# GPS_radiologger_v24_L70_CMWX_MAX_v9.net
KiCad netlist of a schematic drawn in EAGLE
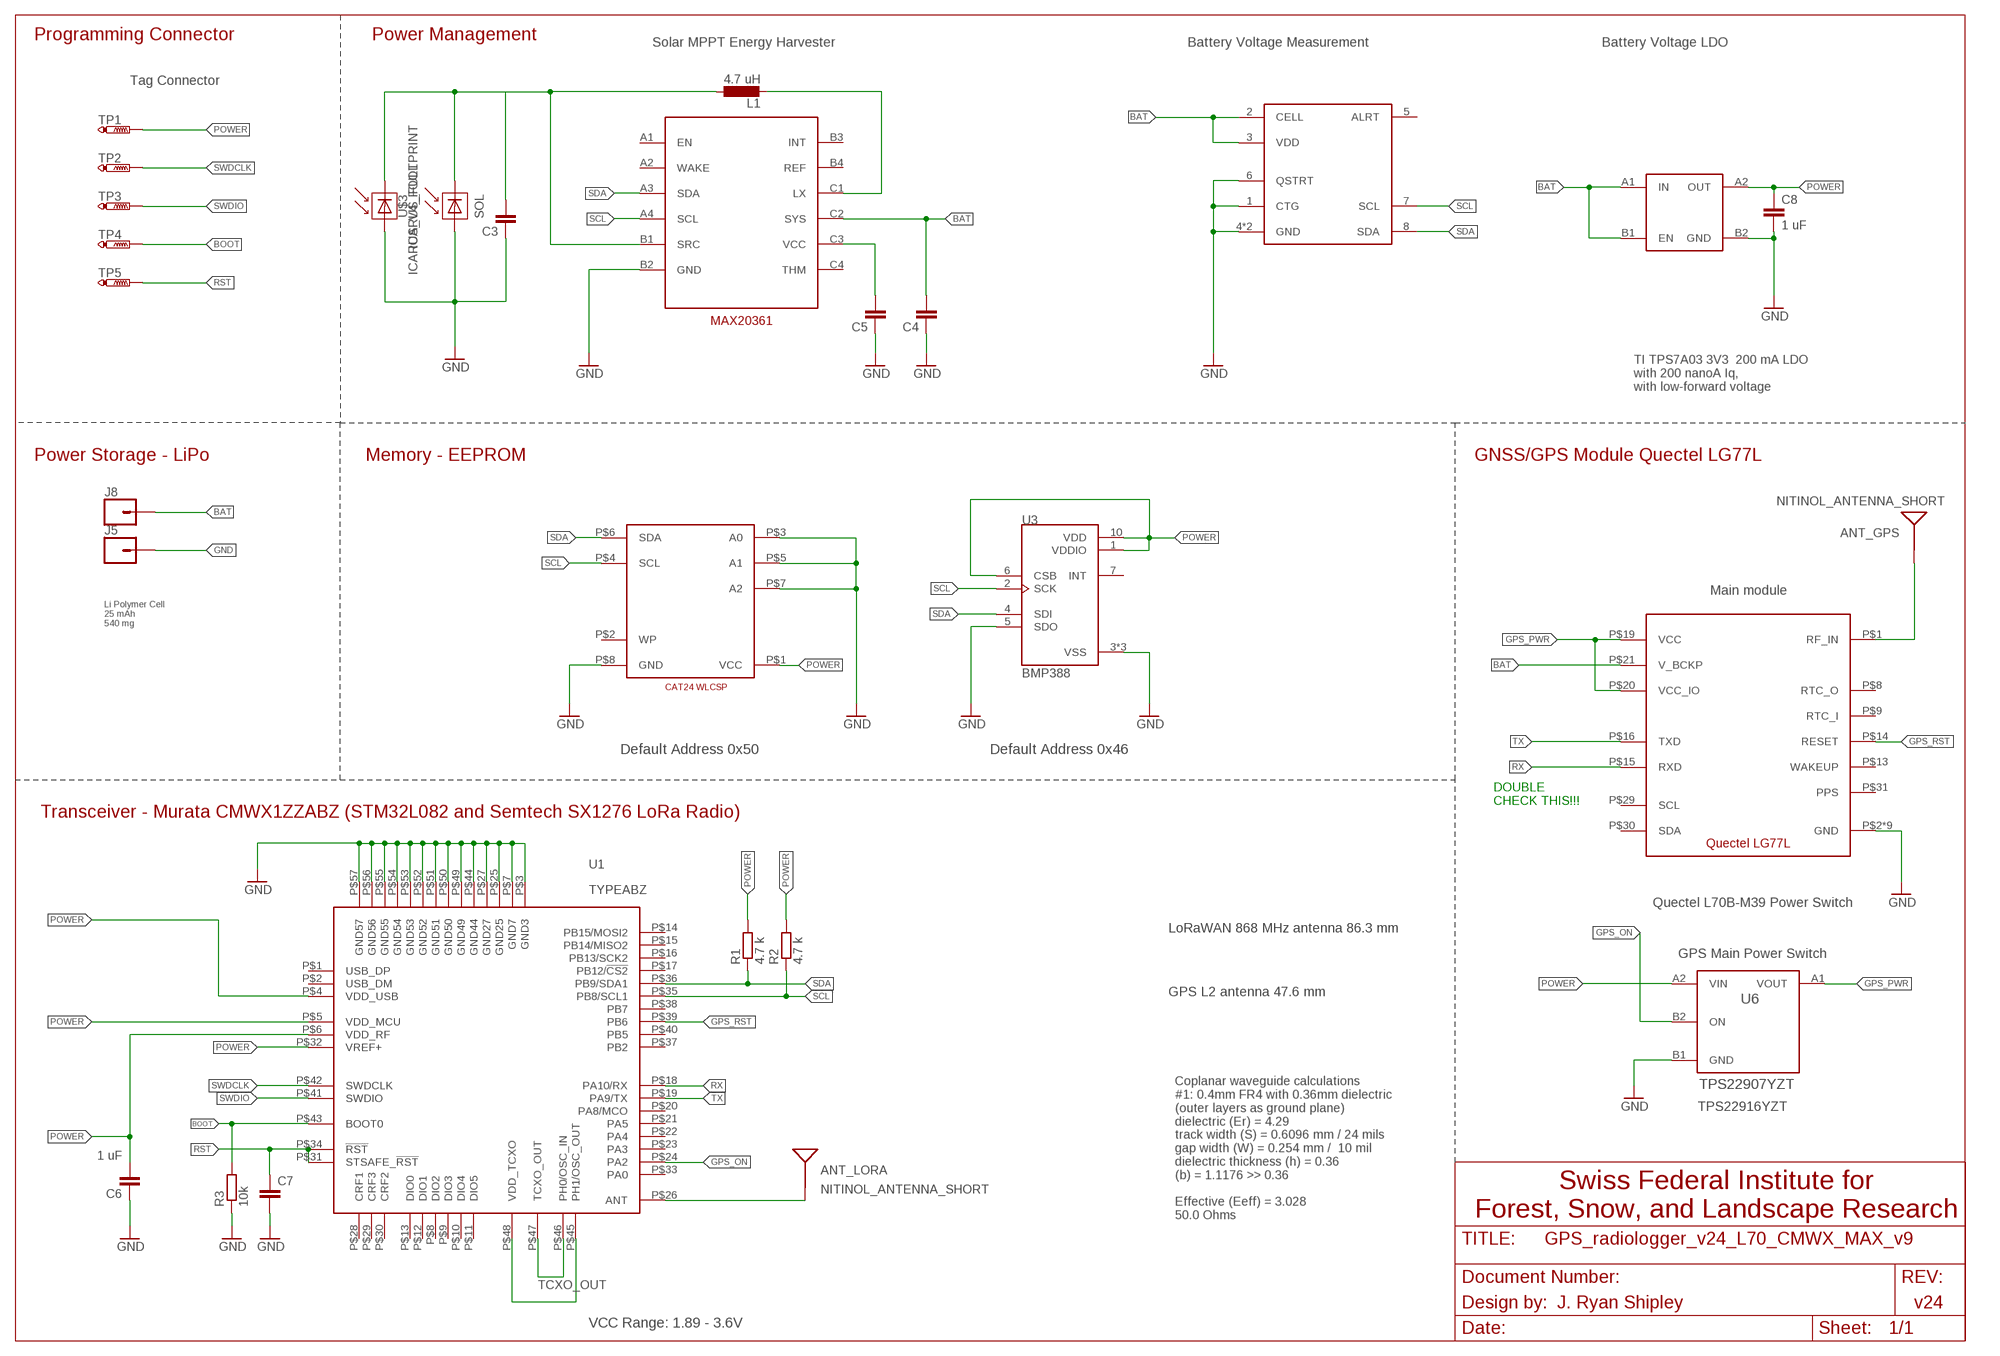
[diagram p0: schematic, sheet 1]

(export (version "E")
  (design (tool "Eeschema 10.0.6"))
  (components
    (comp (ref "ANT_GPS")
      (value "NITINOL_ANTENNA_SHORT")
      (footprint "eagle-import:ICARUS_NITINOL_ANTENNA_SHORT")
      (libsource (lib "eagle-import") (part "NITINOL_ANTENNA_SHORT"))
    )
    (comp (ref "ANT_LORA")
      (value "NITINOL_ANTENNA_SHORT")
      (footprint "eagle-import:ICARUS_NITINOL_ANTENNA_SHORT")
      (libsource (lib "eagle-import") (part "NITINOL_ANTENNA_SHORT"))
    )
    (comp (ref "C3")
      (value "10UF")
      (footprint "eagle-import:0603-TIGHT")
      (libsource (lib "eagle-import") (part "10UF"))
    )
    (comp (ref "C4")
      (value "1.0UF")
      (footprint "eagle-import:0402-TIGHTER")
      (libsource (lib "eagle-import") (part "1.0UF"))
    )
    (comp (ref "C5")
      (value "1.0UF")
      (footprint "eagle-import:0402-TIGHTER")
      (libsource (lib "eagle-import") (part "1.0UF"))
    )
    (comp (ref "C6")
      (value "1 uF")
      (footprint "eagle-import:0402-TIGHTER")
      (libsource (lib "eagle-import") (part "1.0UF"))
    )
    (comp (ref "C7")
      (value "C-EUC0201")
      (footprint "eagle-import:C0201")
      (libsource (lib "eagle-import") (part "C-EUC0201"))
    )
    (comp (ref "C8")
      (value "1 uF")
      (footprint "eagle-import:0402-TIGHTER")
      (libsource (lib "eagle-import") (part "1.0UF"))
    )
    (comp (ref "J5")
      (value "CONN_01PTH_NO_SILK_SMALL")
      (footprint "eagle-import:1X01_SMALL")
      (libsource (lib "eagle-import") (part "CONN_01PTH_NO_SILK_SMALL"))
    )
    (comp (ref "J8")
      (value "CONN_01PTH_NO_SILK_SMALL")
      (footprint "eagle-import:1X01_SMALL")
      (libsource (lib "eagle-import") (part "CONN_01PTH_NO_SILK_SMALL"))
    )
    (comp (ref "L1")
      (value "4.7 uH")
      (footprint "eagle-import:INDC2016X120L")
      (libsource (lib "eagle-import") (part "IND_2016"))
    )
    (comp (ref "R1")
      (value "4.7 k")
      (footprint "eagle-import:R0201")
      (libsource (lib "eagle-import") (part "R-EU_R0201"))
    )
    (comp (ref "R2")
      (value "4.7 k")
      (footprint "eagle-import:R0201")
      (libsource (lib "eagle-import") (part "R-EU_R0201"))
    )
    (comp (ref "R3")
      (value "10k")
      (footprint "eagle-import:R0201")
      (libsource (lib "eagle-import") (part "R-EU_R0201"))
    )
    (comp (ref "SOL")
      (value "ICARUS_V4_FOOTPRINT")
      (footprint "eagle-import:ICARUS_FULL_FOOTPRINT")
      (libsource (lib "eagle-import") (part "ICARUS_V4_FOOTPRINT"))
    )
    (comp (ref "TP1")
      (value "PTR1TP08SQ")
      (footprint "eagle-import:TP08SQ")
      (libsource (lib "eagle-import") (part "PTR1TP08SQ"))
    )
    (comp (ref "TP2")
      (value "PTR1TP08SQ")
      (footprint "eagle-import:TP08SQ")
      (libsource (lib "eagle-import") (part "PTR1TP08SQ"))
    )
    (comp (ref "TP3")
      (value "PTR1TP08SQ")
      (footprint "eagle-import:TP08SQ")
      (libsource (lib "eagle-import") (part "PTR1TP08SQ"))
    )
    (comp (ref "TP4")
      (value "PTR1TP08SQ")
      (footprint "eagle-import:TP08SQ")
      (libsource (lib "eagle-import") (part "PTR1TP08SQ"))
    )
    (comp (ref "TP5")
      (value "PTR1TP08SQ")
      (footprint "eagle-import:TP08SQ")
      (libsource (lib "eagle-import") (part "PTR1TP08SQ"))
    )
    (comp (ref "U$1")
      (value "LG77L")
      (footprint "eagle-import:LG77L")
      (libsource (lib "eagle-import") (part "LG77L"))
    )
    (comp (ref "U$2")
      (value "MAX17048G+")
      (footprint "eagle-import:SON50P200X200X75-9T80X120L")
      (libsource (lib "eagle-import") (part "MAX17048G+"))
    )
    (comp (ref "U$3")
      (value "ICARUS_FULL")
      (footprint "eagle-import:ICARUS_FULL")
      (libsource (lib "eagle-import") (part "ICARUS_FULL"))
    )
    (comp (ref "U1")
      (value "TYPEABZ")
      (footprint "eagle-import:TYPEABZ")
      (libsource (lib "eagle-import") (part "TYPEABZ"))
    )
    (comp (ref "U3")
      (value "BMP388")
      (footprint "eagle-import:PQFN50P200X200X80-10N")
      (fields (field (name "MF") "Bosch Sensortec"))
      (libsource (lib "eagle-import") (part "BMP388"))
    )
    (comp (ref "U4")
      (value "TPS7A03-DSBGA")
      (footprint "eagle-import:BGA4N35P2X2_70X70X40N")
      (libsource (lib "eagle-import") (part "TPS7A03-DSBGA"))
    )
    (comp (ref "U6")
      (value "TPS22907YZT")
      (footprint "eagle-import:YFP0004-DSBGA")
      (libsource (lib "eagle-import") (part "TPS22907YZT"))
    )
    (comp (ref "U7")
      (value "CAT24_WLCSP8")
      (footprint "eagle-import:WLCSP8")
      (libsource (lib "eagle-import") (part "CAT24_WLCSP8"))
    )
    (comp (ref "U8")
      (value "MAX20361")
      (footprint "eagle-import:BGA12N40P4X3_123X163X64N")
      (libsource (lib "eagle-import") (part "MAX20361"))
    )
  )
  (nets
    (net (code "1") (name "/TCXO_OUT") (class "Default")
      (node (ref "U1") (pin "P$46") (pinfunction "PH0/OSC_IN_P$46") (pintype "bidirectional"))
      (node (ref "U1") (pin "P$47") (pinfunction "TCXO_OUT_P$47") (pintype "bidirectional"))
    )
    (net (code "2") (name "BAT") (class "Default")
      (node (ref "C4") (pin "P$2") (pinfunction "2_P$2") (pintype "passive"))
      (node (ref "J8") (pin "P$1") (pinfunction "1_P$1") (pintype "passive"))
      (node (ref "U$1") (pin "P$21") (pinfunction "V_BCKP_P$21") (pintype "bidirectional"))
      (node (ref "U$2") (pin "2") (pinfunction "CELL_2") (pintype "bidirectional"))
      (node (ref "U$2") (pin "3") (pinfunction "VDD_3") (pintype "bidirectional"))
      (node (ref "U4") (pin "A1") (pinfunction "IN_A1") (pintype "bidirectional"))
      (node (ref "U4") (pin "B1") (pinfunction "EN_B1") (pintype "bidirectional"))
      (node (ref "U8") (pin "C2") (pinfunction "SYS_C2") (pintype "bidirectional"))
    )
    (net (code "3") (name "BOOT") (class "Default")
      (node (ref "R3") (pin "2") (pinfunction "2_2") (pintype "passive"))
      (node (ref "TP4") (pin "TP") (pinfunction "TP_TP") (pintype "input"))
      (node (ref "U1") (pin "P$43") (pinfunction "BOOT0_P$43") (pintype "bidirectional"))
    )
    (net (code "4") (name "GND") (class "Default")
      (node (ref "C3") (pin "P$1") (pinfunction "1_P$1") (pintype "passive"))
      (node (ref "C4") (pin "P$1") (pinfunction "1_P$1") (pintype "passive"))
      (node (ref "C5") (pin "P$1") (pinfunction "1_P$1") (pintype "passive"))
      (node (ref "C6") (pin "P$1") (pinfunction "1_P$1") (pintype "passive"))
      (node (ref "C7") (pin "2") (pinfunction "2_2") (pintype "passive"))
      (node (ref "C8") (pin "P$2") (pinfunction "2_P$2") (pintype "passive"))
      (node (ref "J5") (pin "P$1") (pinfunction "1_P$1") (pintype "passive"))
      (node (ref "R3") (pin "1") (pinfunction "1_1") (pintype "passive"))
      (node (ref "SOL") (pin "P$2") (pinfunction "MINUS_P$2") (pintype "passive"))
      (node (ref "U$1") (pin "P$18") (pinfunction "GND_P$18") (pintype "bidirectional"))
      (node (ref "U$1") (pin "P$2") (pinfunction "GND_P$2") (pintype "bidirectional"))
      (node (ref "U$1") (pin "P$37") (pinfunction "GND_P$37") (pintype "bidirectional"))
      (node (ref "U$1") (pin "P$38") (pinfunction "GND_P$38") (pintype "bidirectional"))
      (node (ref "U$1") (pin "P$39") (pinfunction "GND_P$39") (pintype "bidirectional"))
      (node (ref "U$1") (pin "P$40") (pinfunction "GND_P$40") (pintype "bidirectional"))
      (node (ref "U$1") (pin "P$41") (pinfunction "GND_P$41") (pintype "bidirectional"))
      (node (ref "U$1") (pin "P$42") (pinfunction "GND_P$42") (pintype "bidirectional"))
      (node (ref "U$1") (pin "P$43") (pinfunction "GND_P$43") (pintype "bidirectional"))
      (node (ref "U$2") (pin "1") (pinfunction "CTG_1") (pintype "bidirectional"))
      (node (ref "U$2") (pin "4") (pinfunction "GND_4") (pintype "bidirectional"))
      (node (ref "U$2") (pin "6") (pinfunction "QSTRT_6") (pintype "bidirectional"))
      (node (ref "U$2") (pin "9") (pinfunction "GND_9") (pintype "bidirectional"))
      (node (ref "U$3") (pin "P$2") (pinfunction "MINUS_P$2") (pintype "passive"))
      (node (ref "U1") (pin "P$25") (pinfunction "GND25_P$25") (pintype "power_in"))
      (node (ref "U1") (pin "P$27") (pinfunction "GND27_P$27") (pintype "power_in"))
      (node (ref "U1") (pin "P$3") (pinfunction "GND3_P$3") (pintype "power_in"))
      (node (ref "U1") (pin "P$44") (pinfunction "GND44_P$44") (pintype "power_in"))
      (node (ref "U1") (pin "P$49") (pinfunction "GND49_P$49") (pintype "power_in"))
      (node (ref "U1") (pin "P$50") (pinfunction "GND50_P$50") (pintype "power_in"))
      (node (ref "U1") (pin "P$51") (pinfunction "GND51_P$51") (pintype "power_in"))
      (node (ref "U1") (pin "P$52") (pinfunction "GND52_P$52") (pintype "power_in"))
      (node (ref "U1") (pin "P$53") (pinfunction "GND53_P$53") (pintype "power_in"))
      (node (ref "U1") (pin "P$54") (pinfunction "GND54_P$54") (pintype "power_in"))
      (node (ref "U1") (pin "P$55") (pinfunction "GND55_P$55") (pintype "power_in"))
      (node (ref "U1") (pin "P$56") (pinfunction "GND56_P$56") (pintype "power_in"))
      (node (ref "U1") (pin "P$57") (pinfunction "GND57_P$57") (pintype "power_in"))
      (node (ref "U1") (pin "P$7") (pinfunction "GND7_P$7") (pintype "power_in"))
      (node (ref "U3") (pin "3") (pinfunction "VSS_3") (pintype "power_in"))
      (node (ref "U3") (pin "5") (pinfunction "SDO_5") (pintype "bidirectional"))
      (node (ref "U3") (pin "8") (pinfunction "VSS_8") (pintype "power_in"))
      (node (ref "U3") (pin "9") (pinfunction "VSS_9") (pintype "power_in"))
      (node (ref "U4") (pin "B2") (pinfunction "GND_B2") (pintype "bidirectional"))
      (node (ref "U6") (pin "B1") (pinfunction "GND_B1") (pintype "bidirectional"))
      (node (ref "U7") (pin "P$3") (pinfunction "A0_P$3") (pintype "bidirectional"))
      (node (ref "U7") (pin "P$5") (pinfunction "A1_P$5") (pintype "bidirectional"))
      (node (ref "U7") (pin "P$7") (pinfunction "A2_P$7") (pintype "bidirectional"))
      (node (ref "U7") (pin "P$8") (pinfunction "GND_P$8") (pintype "bidirectional"))
      (node (ref "U8") (pin "B2") (pinfunction "GND_B2") (pintype "bidirectional"))
    )
    (net (code "5") (name "GPS_ON") (class "Default")
      (node (ref "U1") (pin "P$24") (pinfunction "PA2_P$24") (pintype "bidirectional"))
      (node (ref "U6") (pin "B2") (pinfunction "ON_B2") (pintype "bidirectional"))
    )
    (net (code "6") (name "GPS_PWR") (class "Default")
      (node (ref "U$1") (pin "P$19") (pinfunction "VCC_P$19") (pintype "bidirectional"))
      (node (ref "U$1") (pin "P$20") (pinfunction "VCC_IO_P$20") (pintype "bidirectional"))
      (node (ref "U6") (pin "A1") (pinfunction "VOUT_A1") (pintype "bidirectional"))
    )
    (net (code "7") (name "GPS_RST") (class "Default")
      (node (ref "U$1") (pin "P$14") (pinfunction "RESET_P$14") (pintype "bidirectional"))
      (node (ref "U1") (pin "P$39") (pinfunction "PB6_P$39") (pintype "bidirectional"))
    )
    (net (code "8") (name "Net-(C3-2)") (class "Default")
      (node (ref "C3") (pin "P$2") (pinfunction "2_P$2") (pintype "passive"))
      (node (ref "L1") (pin "1") (pinfunction "1_1") (pintype "passive"))
      (node (ref "SOL") (pin "P$1") (pinfunction "PLUS_P$1") (pintype "passive"))
      (node (ref "U$3") (pin "P$1") (pinfunction "PLUS_P$1") (pintype "passive"))
      (node (ref "U8") (pin "B1") (pinfunction "SRC_B1") (pintype "bidirectional"))
    )
    (net (code "9") (name "Net-(C5-2)") (class "Default")
      (node (ref "C5") (pin "P$2") (pinfunction "2_P$2") (pintype "passive"))
      (node (ref "U8") (pin "C3") (pinfunction "VCC_C3") (pintype "bidirectional"))
    )
    (net (code "10") (name "Net-(U$1-RF_IN)") (class "Default")
      (node (ref "ANT_GPS") (pin "1") (pinfunction "SIGNAL_1") (pintype "bidirectional"))
      (node (ref "ANT_GPS") (pin "2") (pinfunction "SIGNAL_2") (pintype "bidirectional"))
      (node (ref "ANT_GPS") (pin "3") (pinfunction "SIGNAL_3") (pintype "bidirectional"))
      (node (ref "U$1") (pin "P$1") (pinfunction "RF_IN_P$1") (pintype "bidirectional"))
    )
    (net (code "11") (name "Net-(U1-ANT)") (class "Default")
      (node (ref "ANT_LORA") (pin "1") (pinfunction "SIGNAL_1") (pintype "bidirectional"))
      (node (ref "ANT_LORA") (pin "2") (pinfunction "SIGNAL_2") (pintype "bidirectional"))
      (node (ref "ANT_LORA") (pin "3") (pinfunction "SIGNAL_3") (pintype "bidirectional"))
      (node (ref "U1") (pin "P$26") (pinfunction "ANT_P$26") (pintype "bidirectional"))
    )
    (net (code "12") (name "Net-(U1-PH1{slash}OSC_OUT)") (class "Default")
      (node (ref "U1") (pin "P$45") (pinfunction "PH1/OSC_OUT_P$45") (pintype "bidirectional"))
      (node (ref "U1") (pin "P$48") (pinfunction "VDD_TCXO_P$48") (pintype "power_in"))
    )
    (net (code "13") (name "Net-(U8-LX)") (class "Default")
      (node (ref "L1") (pin "2") (pinfunction "2_2") (pintype "passive"))
      (node (ref "U8") (pin "C1") (pinfunction "LX_C1") (pintype "bidirectional"))
    )
    (net (code "14") (name "POWER") (class "Default")
      (node (ref "C6") (pin "P$2") (pinfunction "2_P$2") (pintype "passive"))
      (node (ref "C8") (pin "P$1") (pinfunction "1_P$1") (pintype "passive"))
      (node (ref "R1") (pin "2") (pinfunction "2_2") (pintype "passive"))
      (node (ref "R2") (pin "2") (pinfunction "2_2") (pintype "passive"))
      (node (ref "TP1") (pin "TP") (pinfunction "TP_TP") (pintype "input"))
      (node (ref "U1") (pin "P$32") (pinfunction "VREF+_P$32") (pintype "power_in"))
      (node (ref "U1") (pin "P$4") (pinfunction "VDD_USB_P$4") (pintype "power_in"))
      (node (ref "U1") (pin "P$5") (pinfunction "VDD_MCU_P$5") (pintype "power_in"))
      (node (ref "U1") (pin "P$6") (pinfunction "VDD_RF_P$6") (pintype "power_in"))
      (node (ref "U3") (pin "1") (pinfunction "VDDIO_1") (pintype "power_in"))
      (node (ref "U3") (pin "10") (pinfunction "VDD_10") (pintype "power_in"))
      (node (ref "U3") (pin "6") (pinfunction "CSB_6") (pintype "input"))
      (node (ref "U4") (pin "A2") (pinfunction "OUT_A2") (pintype "bidirectional"))
      (node (ref "U6") (pin "A2") (pinfunction "VIN_A2") (pintype "bidirectional"))
      (node (ref "U7") (pin "P$1") (pinfunction "VCC_P$1") (pintype "bidirectional"))
    )
    (net (code "15") (name "RST") (class "Default")
      (node (ref "C7") (pin "1") (pinfunction "1_1") (pintype "passive"))
      (node (ref "TP5") (pin "TP") (pinfunction "TP_TP") (pintype "input"))
      (node (ref "U1") (pin "P$31") (pinfunction "STSAFE_~{RST}_P$31") (pintype "bidirectional"))
      (node (ref "U1") (pin "P$34") (pinfunction "~{RST}_P$34") (pintype "bidirectional"))
    )
    (net (code "16") (name "RX") (class "Default")
      (node (ref "U$1") (pin "P$15") (pinfunction "RXD_P$15") (pintype "bidirectional"))
      (node (ref "U1") (pin "P$18") (pinfunction "PA10/RX_P$18") (pintype "bidirectional"))
    )
    (net (code "17") (name "SCL") (class "Default")
      (node (ref "R2") (pin "1") (pinfunction "1_1") (pintype "passive"))
      (node (ref "U$2") (pin "7") (pinfunction "SCL_7") (pintype "bidirectional"))
      (node (ref "U1") (pin "P$35") (pinfunction "PB8/SCL1_P$35") (pintype "bidirectional"))
      (node (ref "U3") (pin "2") (pinfunction "SCK_2") (pintype "input"))
      (node (ref "U7") (pin "P$4") (pinfunction "SCL_P$4") (pintype "bidirectional"))
      (node (ref "U8") (pin "A4") (pinfunction "SCL_A4") (pintype "bidirectional"))
    )
    (net (code "18") (name "SDA") (class "Default")
      (node (ref "R1") (pin "1") (pinfunction "1_1") (pintype "passive"))
      (node (ref "U$2") (pin "8") (pinfunction "SDA_8") (pintype "bidirectional"))
      (node (ref "U1") (pin "P$36") (pinfunction "PB9/SDA1_P$36") (pintype "bidirectional"))
      (node (ref "U3") (pin "4") (pinfunction "SDI_4") (pintype "bidirectional"))
      (node (ref "U7") (pin "P$6") (pinfunction "SDA_P$6") (pintype "bidirectional"))
      (node (ref "U8") (pin "A3") (pinfunction "SDA_A3") (pintype "bidirectional"))
    )
    (net (code "19") (name "SWDCLK") (class "Default")
      (node (ref "TP2") (pin "TP") (pinfunction "TP_TP") (pintype "input"))
      (node (ref "U1") (pin "P$42") (pinfunction "SWDCLK_P$42") (pintype "bidirectional"))
    )
    (net (code "20") (name "SWDIO") (class "Default")
      (node (ref "TP3") (pin "TP") (pinfunction "TP_TP") (pintype "input"))
      (node (ref "U1") (pin "P$41") (pinfunction "SWDIO_P$41") (pintype "bidirectional"))
    )
    (net (code "21") (name "TX") (class "Default")
      (node (ref "U$1") (pin "P$16") (pinfunction "TXD_P$16") (pintype "bidirectional"))
      (node (ref "U1") (pin "P$19") (pinfunction "PA9/TX_P$19") (pintype "bidirectional"))
    )
    (net (code "22") (name "unconnected-(U$1-PPS-PadP$31)") (class "Default")
      (node (ref "U$1") (pin "P$31") (pinfunction "PPS_P$31") (pintype "bidirectional"))
    )
    (net (code "23") (name "unconnected-(U$1-RTC_I-PadP$9)") (class "Default")
      (node (ref "U$1") (pin "P$9") (pinfunction "RTC_I_P$9") (pintype "bidirectional"))
    )
    (net (code "24") (name "unconnected-(U$1-RTC_O-PadP$8)") (class "Default")
      (node (ref "U$1") (pin "P$8") (pinfunction "RTC_O_P$8") (pintype "bidirectional"))
    )
    (net (code "25") (name "unconnected-(U$1-SCL-PadP$29)") (class "Default")
      (node (ref "U$1") (pin "P$29") (pinfunction "SCL_P$29") (pintype "bidirectional"))
    )
    (net (code "26") (name "unconnected-(U$1-SDA-PadP$30)") (class "Default")
      (node (ref "U$1") (pin "P$30") (pinfunction "SDA_P$30") (pintype "bidirectional"))
    )
    (net (code "27") (name "unconnected-(U$1-WAKEUP-PadP$13)") (class "Default")
      (node (ref "U$1") (pin "P$13") (pinfunction "WAKEUP_P$13") (pintype "bidirectional"))
    )
    (net (code "28") (name "unconnected-(U$2-ALRT-Pad5)") (class "Default")
      (node (ref "U$2") (pin "5") (pinfunction "ALRT_5") (pintype "bidirectional"))
    )
    (net (code "29") (name "unconnected-(U1-CRF1-PadP$28)") (class "Default")
      (node (ref "U1") (pin "P$28") (pinfunction "CRF1_P$28") (pintype "no_connect"))
    )
    (net (code "30") (name "unconnected-(U1-CRF2-PadP$30)") (class "Default")
      (node (ref "U1") (pin "P$30") (pinfunction "CRF2_P$30") (pintype "no_connect"))
    )
    (net (code "31") (name "unconnected-(U1-CRF3-PadP$29)") (class "Default")
      (node (ref "U1") (pin "P$29") (pinfunction "CRF3_P$29") (pintype "no_connect"))
    )
    (net (code "32") (name "unconnected-(U1-DIO0-PadP$13)") (class "Default")
      (node (ref "U1") (pin "P$13") (pinfunction "DIO0_P$13") (pintype "no_connect"))
    )
    (net (code "33") (name "unconnected-(U1-DIO1-PadP$12)") (class "Default")
      (node (ref "U1") (pin "P$12") (pinfunction "DIO1_P$12") (pintype "no_connect"))
    )
    (net (code "34") (name "unconnected-(U1-DIO2-PadP$8)") (class "Default")
      (node (ref "U1") (pin "P$8") (pinfunction "DIO2_P$8") (pintype "no_connect"))
    )
    (net (code "35") (name "unconnected-(U1-DIO3-PadP$9)") (class "Default")
      (node (ref "U1") (pin "P$9") (pinfunction "DIO3_P$9") (pintype "no_connect"))
    )
    (net (code "36") (name "unconnected-(U1-DIO4-PadP$10)") (class "Default")
      (node (ref "U1") (pin "P$10") (pinfunction "DIO4_P$10") (pintype "bidirectional"))
    )
    (net (code "37") (name "unconnected-(U1-DIO5-PadP$11)") (class "Default")
      (node (ref "U1") (pin "P$11") (pinfunction "DIO5_P$11") (pintype "bidirectional"))
    )
    (net (code "38") (name "unconnected-(U1-PA0-PadP$33)") (class "Default")
      (node (ref "U1") (pin "P$33") (pinfunction "PA0_P$33") (pintype "bidirectional"))
    )
    (net (code "39") (name "unconnected-(U1-PA3-PadP$23)") (class "Default")
      (node (ref "U1") (pin "P$23") (pinfunction "PA3_P$23") (pintype "bidirectional"))
    )
    (net (code "40") (name "unconnected-(U1-PA4-PadP$22)") (class "Default")
      (node (ref "U1") (pin "P$22") (pinfunction "PA4_P$22") (pintype "bidirectional"))
    )
    (net (code "41") (name "unconnected-(U1-PA5-PadP$21)") (class "Default")
      (node (ref "U1") (pin "P$21") (pinfunction "PA5_P$21") (pintype "bidirectional"))
    )
    (net (code "42") (name "unconnected-(U1-PA8{slash}MCO-PadP$20)") (class "Default")
      (node (ref "U1") (pin "P$20") (pinfunction "PA8/MCO_P$20") (pintype "bidirectional"))
    )
    (net (code "43") (name "unconnected-(U1-PB2-PadP$37)") (class "Default")
      (node (ref "U1") (pin "P$37") (pinfunction "PB2_P$37") (pintype "bidirectional"))
    )
    (net (code "44") (name "unconnected-(U1-PB5-PadP$40)") (class "Default")
      (node (ref "U1") (pin "P$40") (pinfunction "PB5_P$40") (pintype "bidirectional"))
    )
    (net (code "45") (name "unconnected-(U1-PB7-PadP$38)") (class "Default")
      (node (ref "U1") (pin "P$38") (pinfunction "PB7_P$38") (pintype "bidirectional"))
    )
    (net (code "46") (name "unconnected-(U1-PB12{slash}~{CS2}-PadP$17)") (class "Default")
      (node (ref "U1") (pin "P$17") (pinfunction "PB12/~{CS2}_P$17") (pintype "bidirectional"))
    )
    (net (code "47") (name "unconnected-(U1-PB13{slash}SCK2-PadP$16)") (class "Default")
      (node (ref "U1") (pin "P$16") (pinfunction "PB13/SCK2_P$16") (pintype "bidirectional"))
    )
    (net (code "48") (name "unconnected-(U1-PB14{slash}MISO2-PadP$15)") (class "Default")
      (node (ref "U1") (pin "P$15") (pinfunction "PB14/MISO2_P$15") (pintype "bidirectional"))
    )
    (net (code "49") (name "unconnected-(U1-PB15{slash}MOSI2-PadP$14)") (class "Default")
      (node (ref "U1") (pin "P$14") (pinfunction "PB15/MOSI2_P$14") (pintype "bidirectional"))
    )
    (net (code "50") (name "unconnected-(U1-USB_DM-PadP$2)") (class "Default")
      (node (ref "U1") (pin "P$2") (pinfunction "USB_DM_P$2") (pintype "bidirectional"))
    )
    (net (code "51") (name "unconnected-(U1-USB_DP-PadP$1)") (class "Default")
      (node (ref "U1") (pin "P$1") (pinfunction "USB_DP_P$1") (pintype "bidirectional"))
    )
    (net (code "52") (name "unconnected-(U3-INT-Pad7)") (class "Default")
      (node (ref "U3") (pin "7") (pinfunction "INT_7") (pintype "output"))
    )
    (net (code "53") (name "unconnected-(U7-WP-PadP$2)") (class "Default")
      (node (ref "U7") (pin "P$2") (pinfunction "WP_P$2") (pintype "bidirectional"))
    )
    (net (code "54") (name "unconnected-(U8-EN-PadA1)") (class "Default")
      (node (ref "U8") (pin "A1") (pinfunction "EN_A1") (pintype "bidirectional"))
    )
    (net (code "55") (name "unconnected-(U8-INT-PadB3)") (class "Default")
      (node (ref "U8") (pin "B3") (pinfunction "INT_B3") (pintype "bidirectional"))
    )
    (net (code "56") (name "unconnected-(U8-REF-PadB4)") (class "Default")
      (node (ref "U8") (pin "B4") (pinfunction "REF_B4") (pintype "bidirectional"))
    )
    (net (code "57") (name "unconnected-(U8-THM-PadC4)") (class "Default")
      (node (ref "U8") (pin "C4") (pinfunction "THM_C4") (pintype "bidirectional"))
    )
    (net (code "58") (name "unconnected-(U8-WAKE-PadA2)") (class "Default")
      (node (ref "U8") (pin "A2") (pinfunction "WAKE_A2") (pintype "bidirectional"))
    )
  )
)
